# BOSS-RoboClaw-Breakout.net
KiCad netlist of a schematic drawn in EAGLE
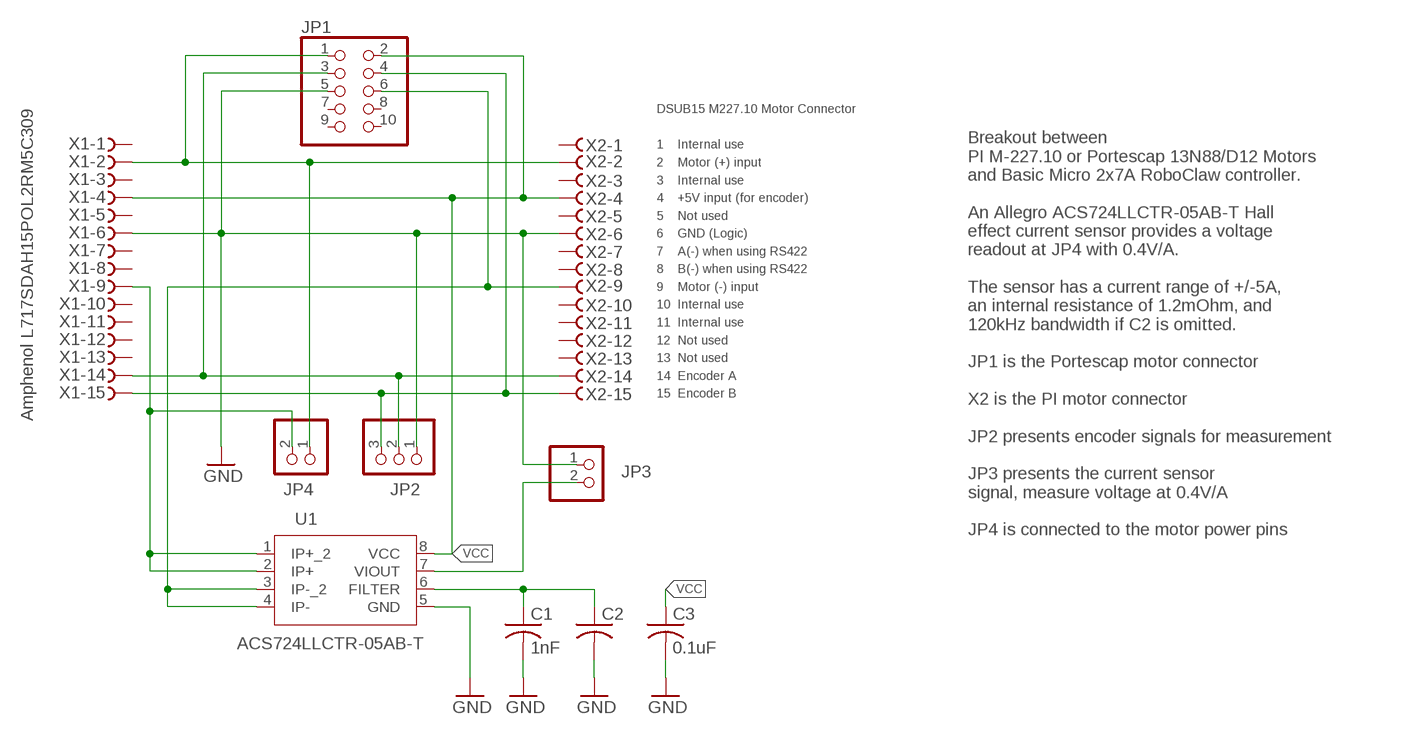
[diagram p0: schematic, sheet 1]

(export (version "E")
  (design (tool "Eeschema 10.0.6"))
  (components
    (comp (ref "C1")
      (value "1nF")
      (footprint "eagle-import:C0805")
      (libsource (lib "eagle-import") (part "C-USC0805"))
    )
    (comp (ref "C2")
      (value "C-USC0805")
      (footprint "eagle-import:C0805")
      (libsource (lib "eagle-import") (part "C-USC0805"))
    )
    (comp (ref "C3")
      (value "0.1uF")
      (footprint "eagle-import:C0805")
      (libsource (lib "eagle-import") (part "C-USC0805"))
    )
    (comp (ref "JP1")
      (value "PINHD-2X5")
      (footprint "eagle-import:2X05")
      (libsource (lib "eagle-import") (part "PINHD-2X5"))
    )
    (comp (ref "JP2")
      (value "PINHD-1X3")
      (footprint "eagle-import:1X03")
      (libsource (lib "eagle-import") (part "PINHD-1X3"))
    )
    (comp (ref "JP3")
      (value "PINHD-1X2")
      (footprint "eagle-import:1X02")
      (libsource (lib "eagle-import") (part "PINHD-1X2"))
    )
    (comp (ref "JP4")
      (value "PINHD-1X2")
      (footprint "eagle-import:1X02")
      (libsource (lib "eagle-import") (part "PINHD-1X2"))
    )
    (comp (ref "U1")
      (value "ACS724LLCTR-05AB-T")
      (footprint "eagle-import:IC8_ACS724LLCTR-05AB-T_ALM")
      (fields (field (name "COPYRIGHT") "Copyright (C) 2018 Accelerated Designs. All rights reserved"))
      (libsource (lib "eagle-import") (part "CURRENTSENSOR-ACS724LLCTR-05AB-T"))
    )
    (comp (ref "X1")
      (value "Amphenol L717SDAH15POL2RM5C309")
      (footprint "eagle-import:H2M15ST")
      (libsource (lib "eagle-import") (part "D-SUB15-H2M15ST"))
    )
    (comp (ref "X2")
      (value "Amphenol L77SDAH15SOL2RM8C309")
      (footprint "eagle-import:H2R15ST")
      (libsource (lib "eagle-import") (part "D-SUB15-H2R15ST"))
    )
  )
  (nets
    (net (code "1") (name "GND") (class "Default")
      (node (ref "C1") (pin "2") (pinfunction "2_2") (pintype "passive"))
      (node (ref "C2") (pin "2") (pinfunction "2_2") (pintype "passive"))
      (node (ref "C3") (pin "2") (pinfunction "2_2") (pintype "passive"))
      (node (ref "JP1") (pin "5") (pinfunction "5_5") (pintype "passive"))
      (node (ref "JP2") (pin "1") (pinfunction "1_1") (pintype "passive"))
      (node (ref "JP3") (pin "1") (pinfunction "1_1") (pintype "passive"))
      (node (ref "U1") (pin "5") (pinfunction "GND_5") (pintype "passive"))
      (node (ref "X1") (pin "6") (pinfunction "F_6") (pintype "passive"))
      (node (ref "X2") (pin "6") (pinfunction "F_6") (pintype "passive"))
    )
    (net (code "2") (name "Net-(U1-FILTER)") (class "Default")
      (node (ref "C1") (pin "1") (pinfunction "1_1") (pintype "passive"))
      (node (ref "C2") (pin "1") (pinfunction "1_1") (pintype "passive"))
      (node (ref "U1") (pin "6") (pinfunction "FILTER_6") (pintype "passive"))
    )
    (net (code "3") (name "Net-(U1-IP+)") (class "Default")
      (node (ref "JP4") (pin "2") (pinfunction "2_2") (pintype "passive"))
      (node (ref "U1") (pin "1") (pinfunction "IP+_2_1") (pintype "passive"))
      (node (ref "U1") (pin "2") (pinfunction "IP+_2") (pintype "passive"))
      (node (ref "X1") (pin "9") (pinfunction "F_9") (pintype "passive"))
    )
    (net (code "4") (name "Net-(U1-IP-)") (class "Default")
      (node (ref "JP1") (pin "6") (pinfunction "6_6") (pintype "passive"))
      (node (ref "U1") (pin "3") (pinfunction "IP-_2_3") (pintype "bidirectional"))
      (node (ref "U1") (pin "4") (pinfunction "IP-_4") (pintype "bidirectional"))
      (node (ref "X2") (pin "9") (pinfunction "F_9") (pintype "passive"))
    )
    (net (code "5") (name "Net-(U1-VIOUT)") (class "Default")
      (node (ref "JP3") (pin "2") (pinfunction "2_2") (pintype "passive"))
      (node (ref "U1") (pin "7") (pinfunction "VIOUT_7") (pintype "output"))
    )
    (net (code "6") (name "Net-(X1F-F)") (class "Default")
      (node (ref "JP1") (pin "3") (pinfunction "3_3") (pintype "passive"))
      (node (ref "JP2") (pin "2") (pinfunction "2_2") (pintype "passive"))
      (node (ref "X1") (pin "14") (pinfunction "F_14") (pintype "passive"))
      (node (ref "X2") (pin "14") (pinfunction "F_14") (pintype "passive"))
    )
    (net (code "7") (name "Net-(X1G-F)") (class "Default")
      (node (ref "JP1") (pin "4") (pinfunction "4_4") (pintype "passive"))
      (node (ref "JP2") (pin "3") (pinfunction "3_3") (pintype "passive"))
      (node (ref "X1") (pin "15") (pinfunction "F_15") (pintype "passive"))
      (node (ref "X2") (pin "15") (pinfunction "F_15") (pintype "passive"))
    )
    (net (code "8") (name "Net-(X1H-F)") (class "Default")
      (node (ref "JP1") (pin "1") (pinfunction "1_1") (pintype "passive"))
      (node (ref "JP4") (pin "1") (pinfunction "1_1") (pintype "passive"))
      (node (ref "X1") (pin "2") (pinfunction "F_2") (pintype "passive"))
      (node (ref "X2") (pin "2") (pinfunction "F_2") (pintype "passive"))
    )
    (net (code "9") (name "VCC") (class "Default")
      (node (ref "C3") (pin "1") (pinfunction "1_1") (pintype "passive"))
      (node (ref "JP1") (pin "2") (pinfunction "2_2") (pintype "passive"))
      (node (ref "U1") (pin "8") (pinfunction "VCC_8") (pintype "power_in"))
      (node (ref "X1") (pin "4") (pinfunction "F_4") (pintype "passive"))
      (node (ref "X2") (pin "4") (pinfunction "F_4") (pintype "passive"))
    )
    (net (code "10") (name "unconnected-(JP1-Pad7)") (class "Default")
      (node (ref "JP1") (pin "7") (pinfunction "7_7") (pintype "passive"))
    )
    (net (code "11") (name "unconnected-(JP1-Pad8)") (class "Default")
      (node (ref "JP1") (pin "8") (pinfunction "8_8") (pintype "passive"))
    )
    (net (code "12") (name "unconnected-(JP1-Pad9)") (class "Default")
      (node (ref "JP1") (pin "9") (pinfunction "9_9") (pintype "passive"))
    )
    (net (code "13") (name "unconnected-(JP1-Pad10)") (class "Default")
      (node (ref "JP1") (pin "10") (pinfunction "10_10") (pintype "passive"))
    )
    (net (code "14") (name "unconnected-(X1A-F-Pad1)") (class "Default")
      (node (ref "X1") (pin "1") (pinfunction "F_1") (pintype "passive"))
    )
    (net (code "15") (name "unconnected-(X1B-F-Pad10)") (class "Default")
      (node (ref "X1") (pin "10") (pinfunction "F_10") (pintype "passive"))
    )
    (net (code "16") (name "unconnected-(X1C-F-Pad11)") (class "Default")
      (node (ref "X1") (pin "11") (pinfunction "F_11") (pintype "passive"))
    )
    (net (code "17") (name "unconnected-(X1D-F-Pad12)") (class "Default")
      (node (ref "X1") (pin "12") (pinfunction "F_12") (pintype "passive"))
    )
    (net (code "18") (name "unconnected-(X1E-F-Pad13)") (class "Default")
      (node (ref "X1") (pin "13") (pinfunction "F_13") (pintype "passive"))
    )
    (net (code "19") (name "unconnected-(X1I-F-Pad3)") (class "Default")
      (node (ref "X1") (pin "3") (pinfunction "F_3") (pintype "passive"))
    )
    (net (code "20") (name "unconnected-(X1K-F-Pad5)") (class "Default")
      (node (ref "X1") (pin "5") (pinfunction "F_5") (pintype "passive"))
    )
    (net (code "21") (name "unconnected-(X1M-F-Pad7)") (class "Default")
      (node (ref "X1") (pin "7") (pinfunction "F_7") (pintype "passive"))
    )
    (net (code "22") (name "unconnected-(X1N-F-Pad8)") (class "Default")
      (node (ref "X1") (pin "8") (pinfunction "F_8") (pintype "passive"))
    )
    (net (code "23") (name "unconnected-(X2A-F-Pad1)") (class "Default")
      (node (ref "X2") (pin "1") (pinfunction "F_1") (pintype "passive"))
    )
    (net (code "24") (name "unconnected-(X2B-F-Pad10)") (class "Default")
      (node (ref "X2") (pin "10") (pinfunction "F_10") (pintype "passive"))
    )
    (net (code "25") (name "unconnected-(X2C-F-Pad11)") (class "Default")
      (node (ref "X2") (pin "11") (pinfunction "F_11") (pintype "passive"))
    )
    (net (code "26") (name "unconnected-(X2D-F-Pad12)") (class "Default")
      (node (ref "X2") (pin "12") (pinfunction "F_12") (pintype "passive"))
    )
    (net (code "27") (name "unconnected-(X2E-F-Pad13)") (class "Default")
      (node (ref "X2") (pin "13") (pinfunction "F_13") (pintype "passive"))
    )
    (net (code "28") (name "unconnected-(X2I-F-Pad3)") (class "Default")
      (node (ref "X2") (pin "3") (pinfunction "F_3") (pintype "passive"))
    )
    (net (code "29") (name "unconnected-(X2K-F-Pad5)") (class "Default")
      (node (ref "X2") (pin "5") (pinfunction "F_5") (pintype "passive"))
    )
    (net (code "30") (name "unconnected-(X2M-F-Pad7)") (class "Default")
      (node (ref "X2") (pin "7") (pinfunction "F_7") (pintype "passive"))
    )
    (net (code "31") (name "unconnected-(X2N-F-Pad8)") (class "Default")
      (node (ref "X2") (pin "8") (pinfunction "F_8") (pintype "passive"))
    )
  )
)
